# ProDoc_Schematic1_2025-12-06.net
KiCad netlist of a schematic drawn in EasyEDA Pro
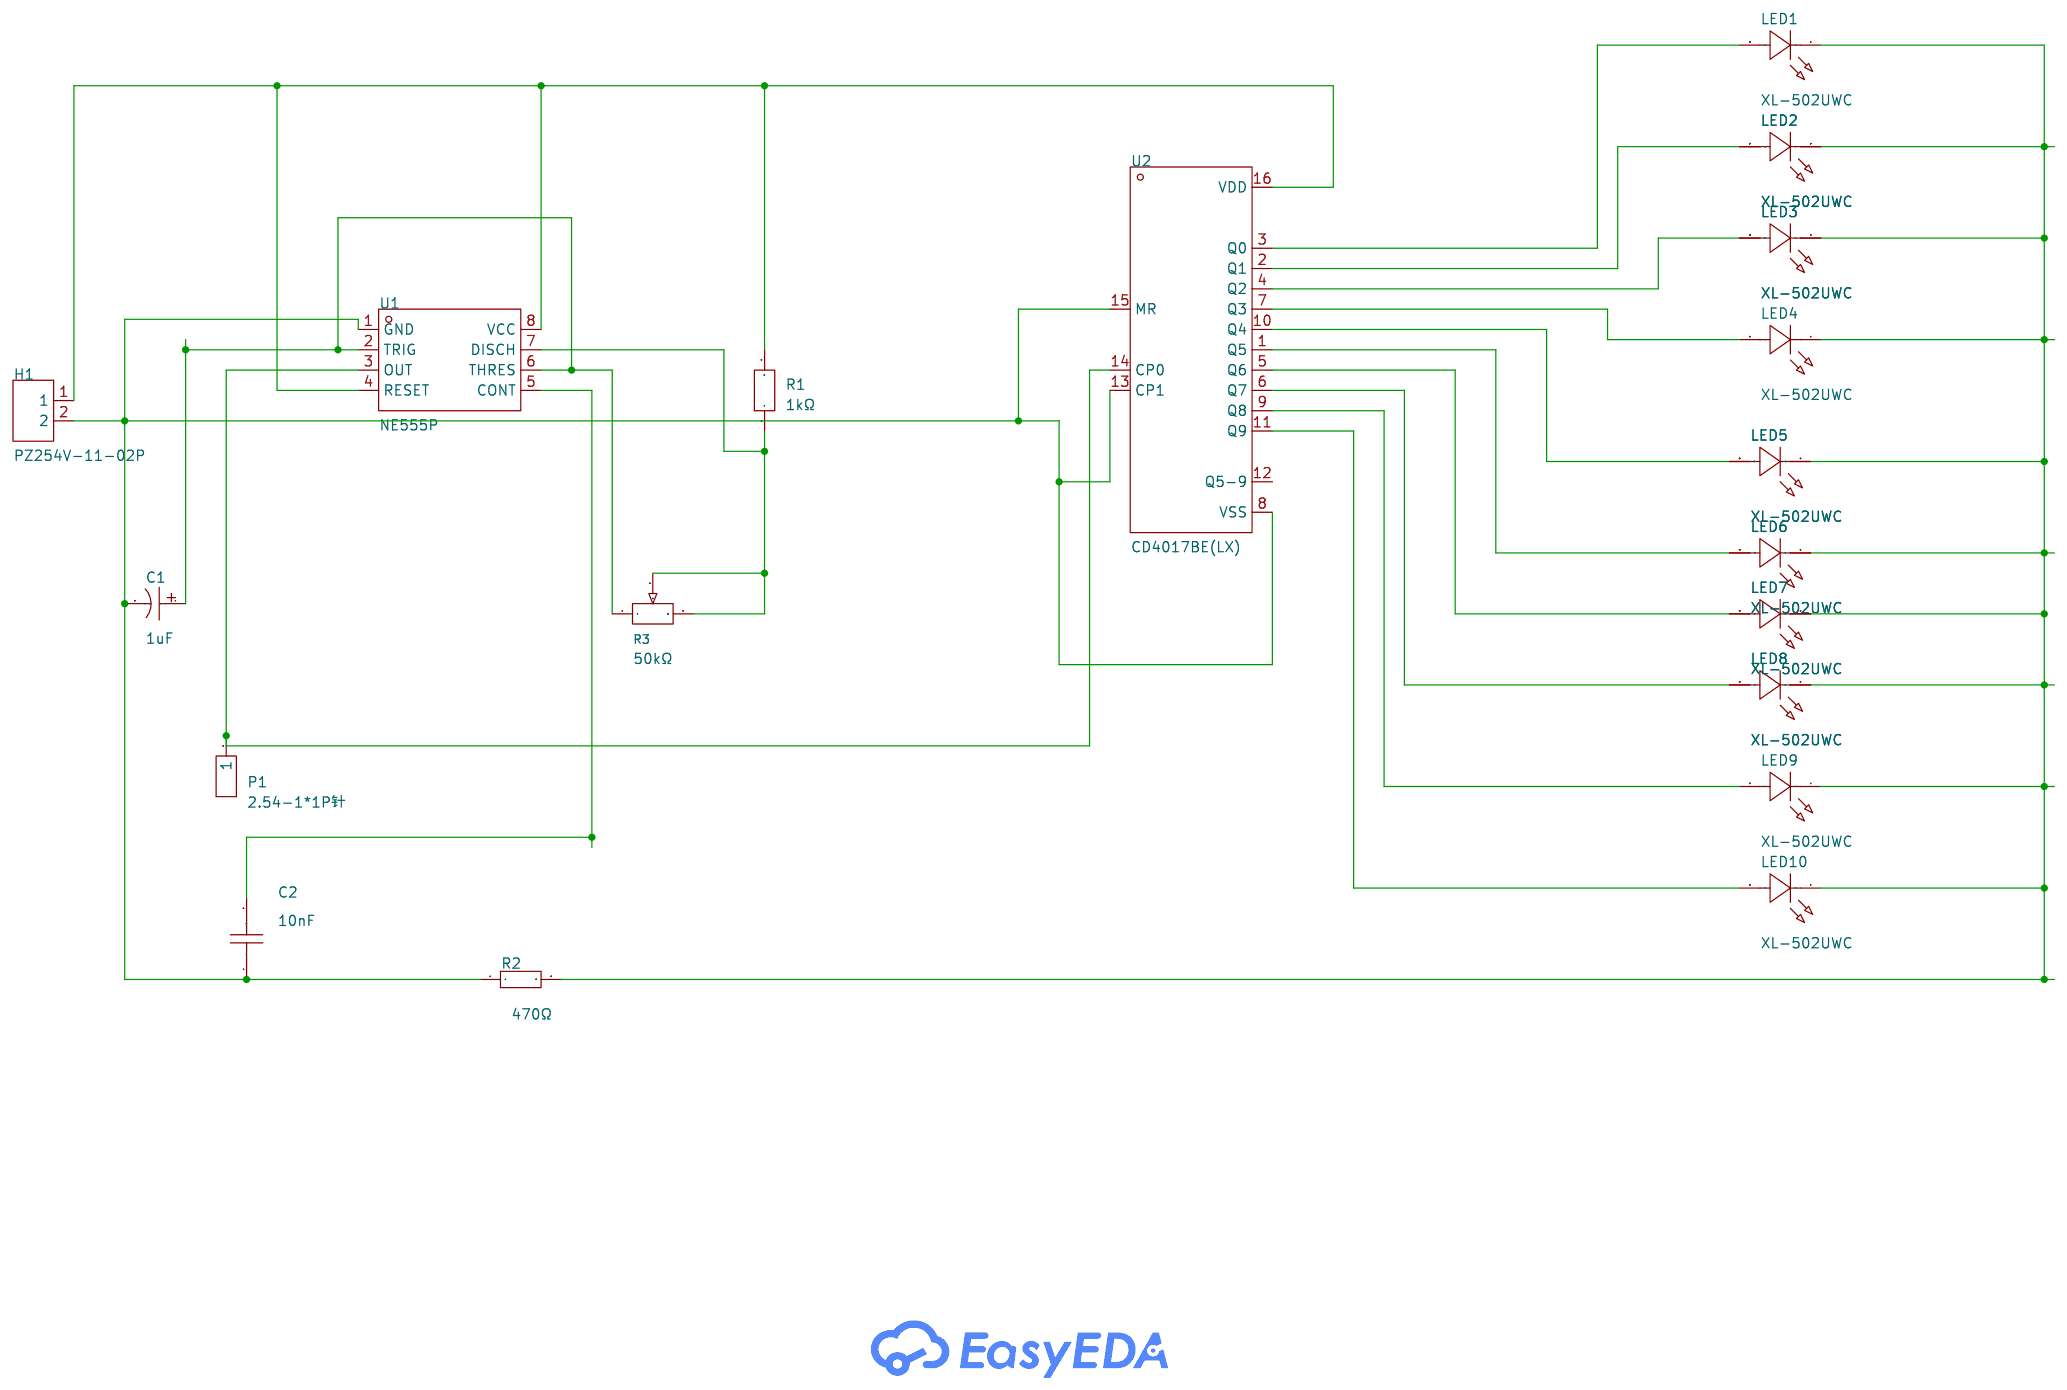
[diagram p0: schematic sheet]

(export (version "E")
  (design (tool "Eeschema 10.0.6"))
  (components
    (comp (ref "C1")
      (value "1uF")
      (footprint "easyedapro:CAP-TH_BD5.0-P2.00-D0.8-FD")
      (fields (field (name "Manufacturer Part") "KF010M050C110A") (field (name "Manufacturer") "CapXon(丰宾)"))
      (libsource (lib "easyedapro") (part "KF010M050C110A"))
    )
    (comp (ref "C2")
      (value "10nF")
      (footprint "easyedapro:CAP-TH_L8.0-W4.0-P5.00-D1.2")
      (fields (field (name "Manufacturer Part") "N09F1B103MN0B0S0N0") (field (name "Manufacturer") "STE(松田)"))
      (libsource (lib "easyedapro") (part "N09F1B103MN0B0S0N0"))
    )
    (comp (ref "H1")
      (value "PZ254V-11-02P")
      (footprint "easyedapro:HDR-TH_2P-P2.54-V-M")
      (fields (field (name "Manufacturer") "XFCN(兴飞)"))
      (libsource (lib "easyedapro") (part "PZ254V-11-02P"))
    )
    (comp (ref "LED1")
      (value "XL-502UWC")
      (footprint "easyedapro:LED-TH_BD5.9-P2.54-RD_WHITE")
      (fields (field (name "Manufacturer") "XINGLIGHT(成兴光)"))
      (libsource (lib "easyedapro") (part "XL-502UWC"))
    )
    (comp (ref "LED2")
      (value "XL-502UWC")
      (footprint "easyedapro:LED-TH_BD5.9-P2.54-RD_WHITE")
      (fields (field (name "Manufacturer") "XINGLIGHT(成兴光)"))
      (libsource (lib "easyedapro") (part "XL-502UWC"))
    )
    (comp (ref "LED3")
      (value "XL-502UWC")
      (footprint "easyedapro:LED-TH_BD5.9-P2.54-RD_WHITE")
      (fields (field (name "Manufacturer") "XINGLIGHT(成兴光)"))
      (libsource (lib "easyedapro") (part "XL-502UWC"))
    )
    (comp (ref "LED4")
      (value "XL-502UWC")
      (footprint "easyedapro:LED-TH_BD5.9-P2.54-RD_WHITE")
      (fields (field (name "Manufacturer") "XINGLIGHT(成兴光)"))
      (libsource (lib "easyedapro") (part "XL-502UWC"))
    )
    (comp (ref "LED5")
      (value "XL-502UWC")
      (footprint "easyedapro:LED-TH_BD5.9-P2.54-RD_WHITE")
      (fields (field (name "Manufacturer") "XINGLIGHT(成兴光)"))
      (libsource (lib "easyedapro") (part "XL-502UWC"))
    )
    (comp (ref "LED6")
      (value "XL-502UWC")
      (footprint "easyedapro:LED-TH_BD5.9-P2.54-RD_WHITE")
      (fields (field (name "Manufacturer") "XINGLIGHT(成兴光)"))
      (libsource (lib "easyedapro") (part "XL-502UWC"))
    )
    (comp (ref "LED7")
      (value "XL-502UWC")
      (footprint "easyedapro:LED-TH_BD5.9-P2.54-RD_WHITE")
      (fields (field (name "Manufacturer") "XINGLIGHT(成兴光)"))
      (libsource (lib "easyedapro") (part "XL-502UWC"))
    )
    (comp (ref "LED8")
      (value "XL-502UWC")
      (footprint "easyedapro:LED-TH_BD5.9-P2.54-RD_WHITE")
      (fields (field (name "Manufacturer") "XINGLIGHT(成兴光)"))
      (libsource (lib "easyedapro") (part "XL-502UWC"))
    )
    (comp (ref "LED9")
      (value "XL-502UWC")
      (footprint "easyedapro:LED-TH_BD5.9-P2.54-RD_WHITE")
      (fields (field (name "Manufacturer") "XINGLIGHT(成兴光)"))
      (libsource (lib "easyedapro") (part "XL-502UWC"))
    )
    (comp (ref "LED10")
      (value "XL-502UWC")
      (footprint "easyedapro:LED-TH_BD5.9-P2.54-RD_WHITE")
      (fields (field (name "Manufacturer") "XINGLIGHT(成兴光)"))
      (libsource (lib "easyedapro") (part "XL-502UWC"))
    )
    (comp (ref "P1")
      (value "2.54-1*1P针")
      (footprint "easyedapro:HDR-TH_1P-P2.54-V-M")
      (fields (field (name "Manufacturer") "BOOMELE(博穆精密)"))
      (libsource (lib "easyedapro") (part "Header-Male-2.54_1x1"))
    )
    (comp (ref "R1")
      (value "1kΩ")
      (footprint "easyedapro:RES-TH_BD2.3-L6.5-P10.50-D0.5")
      (fields (field (name "Manufacturer Part") "MF1/4W-1KΩ±1%T52") (field (name "Manufacturer") "华星机电"))
      (libsource (lib "easyedapro") (part "MF1/4W-1KΩ±1%T52"))
    )
    (comp (ref "R2")
      (value "470Ω")
      (footprint "easyedapro:RES-TH_BD2.2-L6.5-P10.50-D0.6")
      (fields
        (field (name "Manufacturer Part") "MFR0W4F4700A50")
        (field (name "Manufacturer") "UNI-ROYAL(厚声)")
      )
      (libsource (lib "easyedapro") (part "MFR0W4F4700A50"))
    )
    (comp (ref "R3")
      (value "50kΩ")
      (footprint "easyedapro:RES-ADJ-TH_3P-L9.5-W4.85-P2.50-BL-L")
      (fields (field (name "Manufacturer Part") "3296X-1-503") (field (name "Manufacturer") "BOCHEN(博晨)"))
      (libsource (lib "easyedapro") (part "3296X-1-503_C118912"))
    )
    (comp (ref "U1")
      (value "NE555P")
      (footprint "easyedapro:DIP-8_L9.8-W6.6-P2.54-LS7.6-BL")
      (fields (field (name "Manufacturer") "TI(德州仪器)"))
      (libsource (lib "easyedapro") (part "NE555P"))
    )
    (comp (ref "U2")
      (value "CD4017BE(LX)")
      (footprint "easyedapro:PDIP-16_L19.3-W6.4-P2.54-LS7.94-BL")
      (fields (field (name "Manufacturer") "LX(灵星芯微)"))
      (libsource (lib "easyedapro") (part "CD4017BE(LX)"))
    )
  )
  (nets
    (net (code "1") (name "Net-(LED1-A)") (class "Default")
      (node (ref "LED1") (pin "2") (pinfunction "A_2") (pintype "unspecified"))
      (node (ref "U2") (pin "3") (pinfunction "Q0_3") (pintype "unspecified"))
    )
    (net (code "2") (name "Net-(LED1-K)") (class "Default")
      (node (ref "LED1") (pin "1") (pinfunction "K_1") (pintype "unspecified"))
      (node (ref "LED10") (pin "1") (pinfunction "K_1") (pintype "unspecified"))
      (node (ref "LED2") (pin "1") (pinfunction "K_1") (pintype "unspecified"))
      (node (ref "LED3") (pin "1") (pinfunction "K_1") (pintype "unspecified"))
      (node (ref "LED4") (pin "1") (pinfunction "K_1") (pintype "unspecified"))
      (node (ref "LED5") (pin "1") (pinfunction "K_1") (pintype "unspecified"))
      (node (ref "LED6") (pin "1") (pinfunction "K_1") (pintype "unspecified"))
      (node (ref "LED7") (pin "1") (pinfunction "K_1") (pintype "unspecified"))
      (node (ref "LED8") (pin "1") (pinfunction "K_1") (pintype "unspecified"))
      (node (ref "LED9") (pin "1") (pinfunction "K_1") (pintype "unspecified"))
      (node (ref "R2") (pin "2") (pinfunction "2_2") (pintype "input"))
    )
    (net (code "3") (name "Net-(LED2-A)") (class "Default")
      (node (ref "LED2") (pin "2") (pinfunction "A_2") (pintype "unspecified"))
      (node (ref "U2") (pin "2") (pinfunction "Q1_2") (pintype "unspecified"))
    )
    (net (code "4") (name "Net-(LED3-A)") (class "Default")
      (node (ref "LED3") (pin "2") (pinfunction "A_2") (pintype "unspecified"))
      (node (ref "U2") (pin "4") (pinfunction "Q2_4") (pintype "unspecified"))
    )
    (net (code "5") (name "Net-(LED4-A)") (class "Default")
      (node (ref "LED4") (pin "2") (pinfunction "A_2") (pintype "unspecified"))
      (node (ref "U2") (pin "7") (pinfunction "Q3_7") (pintype "unspecified"))
    )
    (net (code "6") (name "Net-(LED5-A)") (class "Default")
      (node (ref "LED5") (pin "2") (pinfunction "A_2") (pintype "unspecified"))
      (node (ref "U2") (pin "10") (pinfunction "Q4_10") (pintype "unspecified"))
    )
    (net (code "7") (name "Net-(LED6-A)") (class "Default")
      (node (ref "LED6") (pin "2") (pinfunction "A_2") (pintype "unspecified"))
      (node (ref "U2") (pin "1") (pinfunction "Q5_1") (pintype "unspecified"))
    )
    (net (code "8") (name "Net-(LED7-A)") (class "Default")
      (node (ref "LED7") (pin "2") (pinfunction "A_2") (pintype "unspecified"))
      (node (ref "U2") (pin "5") (pinfunction "Q6_5") (pintype "unspecified"))
    )
    (net (code "9") (name "Net-(LED8-A)") (class "Default")
      (node (ref "LED8") (pin "2") (pinfunction "A_2") (pintype "unspecified"))
      (node (ref "U2") (pin "6") (pinfunction "Q7_6") (pintype "unspecified"))
    )
    (net (code "10") (name "Net-(LED9-A)") (class "Default")
      (node (ref "LED9") (pin "2") (pinfunction "A_2") (pintype "unspecified"))
      (node (ref "U2") (pin "9") (pinfunction "Q8_9") (pintype "unspecified"))
    )
    (net (code "11") (name "Net-(LED10-A)") (class "Default")
      (node (ref "LED10") (pin "2") (pinfunction "A_2") (pintype "unspecified"))
      (node (ref "U2") (pin "11") (pinfunction "Q9_11") (pintype "unspecified"))
    )
    (net (code "12") (name "Net-(U1-CONT)") (class "Default")
      (node (ref "C2") (pin "2") (pinfunction "2_2") (pintype "unspecified"))
      (node (ref "U1") (pin "5") (pinfunction "CONT_5") (pintype "input"))
    )
    (net (code "13") (name "Net-(U1-DISCH)") (class "Default")
      (node (ref "R1") (pin "1") (pinfunction "1_1") (pintype "unspecified"))
      (node (ref "R3") (pin "2") (pinfunction "2_2") (pintype "input"))
      (node (ref "R3") (pin "3") (pinfunction "3_3") (pintype "input"))
      (node (ref "U1") (pin "7") (pinfunction "DISCH_7") (pintype "input"))
    )
    (net (code "14") (name "Net-(U1-GND)") (class "Default")
      (node (ref "C1") (pin "2") (pinfunction "2_2") (pintype "input"))
      (node (ref "C2") (pin "1") (pinfunction "1_1") (pintype "unspecified"))
      (node (ref "H1") (pin "2") (pinfunction "2_2") (pintype "unspecified"))
      (node (ref "R2") (pin "1") (pinfunction "1_1") (pintype "input"))
      (node (ref "U1") (pin "1") (pinfunction "GND_1") (pintype "input"))
      (node (ref "U2") (pin "13") (pinfunction "CP1_13") (pintype "unspecified"))
      (node (ref "U2") (pin "15") (pinfunction "MR_15") (pintype "unspecified"))
      (node (ref "U2") (pin "8") (pinfunction "VSS_8") (pintype "unspecified"))
    )
    (net (code "15") (name "Net-(U1-OUT)") (class "Default")
      (node (ref "P1") (pin "1") (pinfunction "1_1") (pintype "input"))
      (node (ref "U1") (pin "3") (pinfunction "OUT_3") (pintype "input"))
      (node (ref "U2") (pin "14") (pinfunction "CP0_14") (pintype "unspecified"))
    )
    (net (code "16") (name "Net-(U1-RESET)") (class "Default")
      (node (ref "H1") (pin "1") (pinfunction "1_1") (pintype "unspecified"))
      (node (ref "R1") (pin "2") (pinfunction "2_2") (pintype "unspecified"))
      (node (ref "U1") (pin "4") (pinfunction "RESET_4") (pintype "input"))
      (node (ref "U1") (pin "8") (pinfunction "VCC_8") (pintype "input"))
      (node (ref "U2") (pin "16") (pinfunction "VDD_16") (pintype "unspecified"))
    )
    (net (code "17") (name "Net-(U1-THRES)") (class "Default")
      (node (ref "C1") (pin "1") (pinfunction "1_1") (pintype "input"))
      (node (ref "R3") (pin "1") (pinfunction "1_1") (pintype "input"))
      (node (ref "U1") (pin "2") (pinfunction "TRIG_2") (pintype "input"))
      (node (ref "U1") (pin "6") (pinfunction "THRES_6") (pintype "input"))
    )
    (net (code "18") (name "unconnected-(U2-Q5-9-Pad12)") (class "Default")
      (node (ref "U2") (pin "12") (pinfunction "Q5-9_12") (pintype "unspecified"))
    )
  )
)
